# avt953.net
KiCad netlist of a schematic drawn in EAGLE
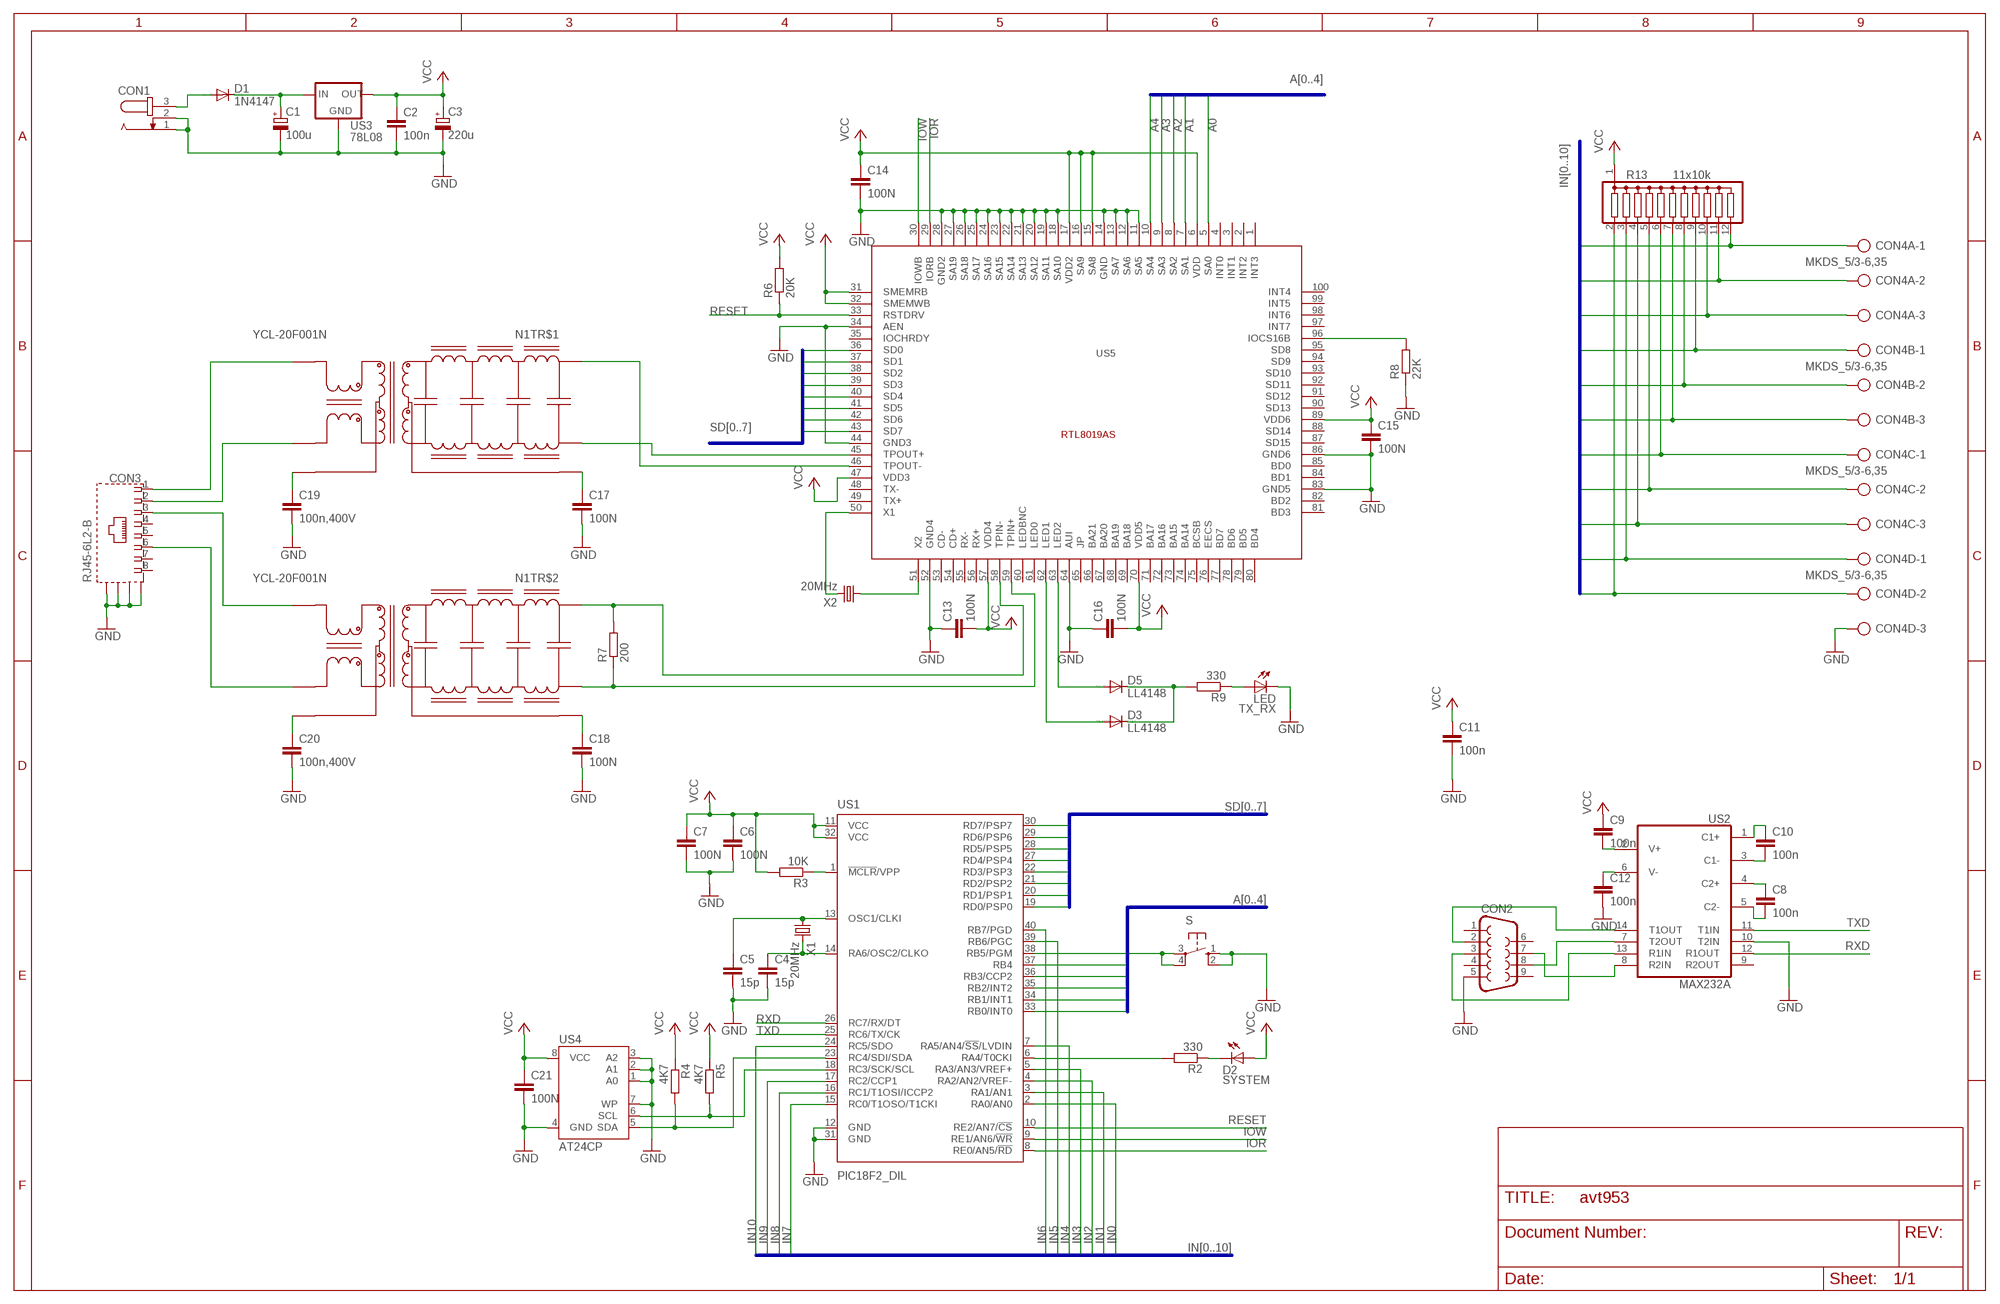
[diagram p0: schematic, sheet 1]

(export (version "E")
  (design (tool "Eeschema 10.0.6"))
  (components
    (comp (ref "C1")
      (value "100u")
      (footprint "eagle-import:TT2D5")
      (libsource (lib "eagle-import") (part "CPOL-EUTT2D5"))
    )
    (comp (ref "C2")
      (value "100n")
      (footprint "eagle-import:C1206K")
      (libsource (lib "eagle-import") (part "C-EUC1206K"))
    )
    (comp (ref "C3")
      (value "220u")
      (footprint "eagle-import:TT2D5")
      (libsource (lib "eagle-import") (part "CPOL-EUTT2D5"))
    )
    (comp (ref "C4")
      (value "15p")
      (footprint "eagle-import:C1206K")
      (libsource (lib "eagle-import") (part "C-EUC1206K"))
    )
    (comp (ref "C5")
      (value "15p")
      (footprint "eagle-import:C1206K")
      (libsource (lib "eagle-import") (part "C-EUC1206K"))
    )
    (comp (ref "C6")
      (value "100N")
      (footprint "eagle-import:C1206K")
      (libsource (lib "eagle-import") (part "C-EUC1206K"))
    )
    (comp (ref "C7")
      (value "100N")
      (footprint "eagle-import:C1206K")
      (libsource (lib "eagle-import") (part "C-EUC1206K"))
    )
    (comp (ref "C8")
      (value "100n")
      (footprint "eagle-import:C1206K")
      (libsource (lib "eagle-import") (part "C-EUC1206K"))
    )
    (comp (ref "C9")
      (value "100n")
      (footprint "eagle-import:C1206K")
      (libsource (lib "eagle-import") (part "C-EUC1206K"))
    )
    (comp (ref "C10")
      (value "100n")
      (footprint "eagle-import:C1206K")
      (libsource (lib "eagle-import") (part "C-EUC1206K"))
    )
    (comp (ref "C11")
      (value "100n")
      (footprint "eagle-import:C1206K")
      (libsource (lib "eagle-import") (part "C-EUC1206K"))
    )
    (comp (ref "C12")
      (value "100n")
      (footprint "eagle-import:C1206K")
      (libsource (lib "eagle-import") (part "C-EUC1206K"))
    )
    (comp (ref "C13")
      (value "100N")
      (footprint "eagle-import:C1206K")
      (libsource (lib "eagle-import") (part "C-EUC1206K"))
    )
    (comp (ref "C14")
      (value "100N")
      (footprint "eagle-import:C1206K")
      (libsource (lib "eagle-import") (part "C-EUC1206K"))
    )
    (comp (ref "C15")
      (value "100N")
      (footprint "eagle-import:C1206K")
      (libsource (lib "eagle-import") (part "C-EUC1206K"))
    )
    (comp (ref "C16")
      (value "100N")
      (footprint "eagle-import:C1206K")
      (libsource (lib "eagle-import") (part "C-EUC1206K"))
    )
    (comp (ref "C17")
      (value "100N")
      (footprint "eagle-import:C1206K")
      (libsource (lib "eagle-import") (part "C-EUC1206K"))
    )
    (comp (ref "C18")
      (value "100N")
      (footprint "eagle-import:C1206K")
      (libsource (lib "eagle-import") (part "C-EUC1206K"))
    )
    (comp (ref "C19")
      (value "100n,400V")
      (footprint "eagle-import:C075-032X103")
      (libsource (lib "eagle-import") (part "C-EU075-032X103"))
    )
    (comp (ref "C20")
      (value "100n,400V")
      (footprint "eagle-import:C075-032X103")
      (libsource (lib "eagle-import") (part "C-EU075-032X103"))
    )
    (comp (ref "C21")
      (value "100N")
      (footprint "eagle-import:C1206K")
      (libsource (lib "eagle-import") (part "C-EUC1206K"))
    )
    (comp (ref "CON1")
      (value "JACK-PLUG0")
      (footprint "eagle-import:SPC4077")
      (libsource (lib "eagle-import") (part "JACK-PLUG0"))
    )
    (comp (ref "CON2")
      (value "F09HP")
      (footprint "eagle-import:F09HP")
      (libsource (lib "eagle-import") (part "F09HP"))
    )
    (comp (ref "CON3")
      (value "RJ45-6L2-B")
      (footprint "eagle-import:RJ45-SHIELD2")
      (libsource (lib "eagle-import") (part "RJ452-B-6L"))
    )
    (comp (ref "CON4A")
      (value "MKDS_5/3-6,35")
      (footprint "eagle-import:MKDS_5_3-635")
      (fields (field (name "MF") "FARNELL") (field (name "MPN") "1714968"))
      (libsource (lib "eagle-import") (part "MKDS_5/3-6,35"))
    )
    (comp (ref "CON4B")
      (value "MKDS_5/3-6,35")
      (footprint "eagle-import:MKDS_5_3-635")
      (fields (field (name "MF") "FARNELL") (field (name "MPN") "1714968"))
      (libsource (lib "eagle-import") (part "MKDS_5/3-6,35"))
    )
    (comp (ref "CON4C")
      (value "MKDS_5/3-6,35")
      (footprint "eagle-import:MKDS_5_3-635")
      (fields (field (name "MF") "FARNELL") (field (name "MPN") "1714968"))
      (libsource (lib "eagle-import") (part "MKDS_5/3-6,35"))
    )
    (comp (ref "CON4D")
      (value "MKDS_5/3-6,35")
      (footprint "eagle-import:MKDS_5_3-635")
      (fields (field (name "MF") "FARNELL") (field (name "MPN") "1714968"))
      (libsource (lib "eagle-import") (part "MKDS_5/3-6,35"))
    )
    (comp (ref "D1")
      (value "1N4147")
      (footprint "eagle-import:DO35-10")
      (libsource (lib "eagle-import") (part "1N4148DO35-10"))
    )
    (comp (ref "D2")
      (value "SYSTEM")
      (footprint "eagle-import:LED5MM")
      (libsource (lib "eagle-import") (part "LED5MM"))
    )
    (comp (ref "D3")
      (value "LL4148")
      (footprint "eagle-import:SOD-123_MINI-SMA")
      (libsource (lib "eagle-import") (part "CGRM400-G1"))
    )
    (comp (ref "D5")
      (value "LL4148")
      (footprint "eagle-import:SOD-123_MINI-SMA")
      (libsource (lib "eagle-import") (part "CGRM400-G1"))
    )
    (comp (ref "LED")
      (value "TX_RX")
      (footprint "eagle-import:LED5MM")
      (libsource (lib "eagle-import") (part "LED5MM"))
    )
    (comp (ref "N1")
      (value "YCL-20F001N")
      (footprint "eagle-import:DIP")
      (libsource (lib "eagle-import") (part "YCL-20F001?N"))
    )
    (comp (ref "R2")
      (value "330")
      (footprint "eagle-import:M3216")
      (libsource (lib "eagle-import") (part "R-EU_M3216"))
    )
    (comp (ref "R3")
      (value "10K")
      (footprint "eagle-import:M3216")
      (libsource (lib "eagle-import") (part "R-EU_M3216"))
    )
    (comp (ref "R4")
      (value "4K7")
      (footprint "eagle-import:M3216")
      (libsource (lib "eagle-import") (part "R-EU_M3216"))
    )
    (comp (ref "R5")
      (value "4K7")
      (footprint "eagle-import:M3216")
      (libsource (lib "eagle-import") (part "R-EU_M3216"))
    )
    (comp (ref "R6")
      (value "20K")
      (footprint "eagle-import:M3216")
      (libsource (lib "eagle-import") (part "R-EU_M3216"))
    )
    (comp (ref "R7")
      (value "200")
      (footprint "eagle-import:M3216")
      (libsource (lib "eagle-import") (part "R-EU_M3216"))
    )
    (comp (ref "R8")
      (value "22K")
      (footprint "eagle-import:M3216")
      (libsource (lib "eagle-import") (part "R-EU_M3216"))
    )
    (comp (ref "R9")
      (value "330")
      (footprint "eagle-import:M3216")
      (libsource (lib "eagle-import") (part "R-EU_M3216"))
    )
    (comp (ref "R13")
      (value "11x10k")
      (footprint "eagle-import:SIL12")
      (libsource (lib "eagle-import") (part "G11R"))
    )
    (comp (ref "S")
      (value "10-XX")
      (footprint "eagle-import:B3F-10XX")
      (fields (field (name "MPN") "B3F-1000"))
      (libsource (lib "eagle-import") (part "10-XX"))
    )
    (comp (ref "US1")
      (value "PIC18F2_DIL")
      (footprint "eagle-import:DIL40")
      (libsource (lib "eagle-import") (part "PIC18F2_DIL"))
    )
    (comp (ref "US2")
      (value "MAX232A")
      (footprint "eagle-import:SO16L")
      (fields (field (name "MF") "MAXIM") (field (name "MPN") "MAX232ECWE+"))
      (libsource (lib "eagle-import") (part "MAX232ECWE"))
    )
    (comp (ref "US3")
      (value "78L08")
      (footprint "eagle-import:78XXL")
      (libsource (lib "eagle-import") (part "78XXL"))
    )
    (comp (ref "US4")
      (value "AT24CP")
      (footprint "eagle-import:DIL08")
      (fields (field (name "MPN") "AT24C1024BW-SH-B"))
      (libsource (lib "eagle-import") (part "AT24CP"))
    )
    (comp (ref "US5")
      (value "RTL8019AS")
      (footprint "eagle-import:RTL8019AS")
      (libsource (lib "eagle-import") (part "RTL8019AS"))
    )
    (comp (ref "X1")
      (value "20MHz")
      (footprint "eagle-import:HC49_S")
      (libsource (lib "eagle-import") (part "CRYSTALHC49S"))
    )
    (comp (ref "X2")
      (value "20MHz")
      (footprint "eagle-import:HC49_S")
      (libsource (lib "eagle-import") (part "CRYSTALHC49S"))
    )
  )
  (nets
    (net (code "1") (name "/A0") (class "Default")
      (node (ref "US1") (pin "33") (pinfunction "RB0/INT0_33") (pintype "bidirectional"))
      (node (ref "US5") (pin "5") (pinfunction "SA0_5") (pintype "bidirectional"))
    )
    (net (code "2") (name "/A1") (class "Default")
      (node (ref "US1") (pin "34") (pinfunction "RB1/INT1_34") (pintype "bidirectional"))
      (node (ref "US5") (pin "7") (pinfunction "SA1_7") (pintype "bidirectional"))
    )
    (net (code "3") (name "/A2") (class "Default")
      (node (ref "US1") (pin "35") (pinfunction "RB2/INT2_35") (pintype "bidirectional"))
      (node (ref "US5") (pin "8") (pinfunction "SA2_8") (pintype "bidirectional"))
    )
    (net (code "4") (name "/A3") (class "Default")
      (node (ref "US1") (pin "36") (pinfunction "RB3/CCP2_36") (pintype "bidirectional"))
      (node (ref "US5") (pin "9") (pinfunction "SA3_9") (pintype "bidirectional"))
    )
    (net (code "5") (name "/A4") (class "Default")
      (node (ref "US1") (pin "37") (pinfunction "RB4_37") (pintype "bidirectional"))
      (node (ref "US5") (pin "10") (pinfunction "SA4_10") (pintype "bidirectional"))
    )
    (net (code "7") (name "/IN0") (class "Default")
      (node (ref "CON4A") (pin "1") (pinfunction "KL_1") (pintype "passive"))
      (node (ref "R13") (pin "12") (pinfunction "12_12") (pintype "passive"))
      (node (ref "US1") (pin "2") (pinfunction "RA0/AN0_2") (pintype "bidirectional"))
    )
    (net (code "8") (name "/IN1") (class "Default")
      (node (ref "CON4A") (pin "2") (pinfunction "KL_2") (pintype "passive"))
      (node (ref "R13") (pin "11") (pinfunction "11_11") (pintype "passive"))
      (node (ref "US1") (pin "3") (pinfunction "RA1/AN1_3") (pintype "bidirectional"))
    )
    (net (code "9") (name "/IN2") (class "Default")
      (node (ref "CON4A") (pin "3") (pinfunction "KL_3") (pintype "passive"))
      (node (ref "R13") (pin "10") (pinfunction "10_10") (pintype "passive"))
      (node (ref "US1") (pin "4") (pinfunction "RA2/AN2/VREF-_4") (pintype "bidirectional"))
    )
    (net (code "10") (name "/IN3") (class "Default")
      (node (ref "CON4B") (pin "1") (pinfunction "KL_1") (pintype "passive"))
      (node (ref "R13") (pin "9") (pinfunction "9_9") (pintype "passive"))
      (node (ref "US1") (pin "5") (pinfunction "RA3/AN3/VREF+_5") (pintype "bidirectional"))
    )
    (net (code "11") (name "/IN4") (class "Default")
      (node (ref "CON4B") (pin "2") (pinfunction "KL_2") (pintype "passive"))
      (node (ref "R13") (pin "8") (pinfunction "8_8") (pintype "passive"))
      (node (ref "US1") (pin "7") (pinfunction "RA5/AN4/~{SS}/LVDIN_7") (pintype "bidirectional"))
    )
    (net (code "12") (name "/IN5") (class "Default")
      (node (ref "CON4B") (pin "3") (pinfunction "KL_3") (pintype "passive"))
      (node (ref "R13") (pin "7") (pinfunction "7_7") (pintype "passive"))
      (node (ref "US1") (pin "39") (pinfunction "RB6/PGC_39") (pintype "bidirectional"))
    )
    (net (code "13") (name "/IN6") (class "Default")
      (node (ref "CON4C") (pin "1") (pinfunction "KL_1") (pintype "passive"))
      (node (ref "R13") (pin "6") (pinfunction "6_6") (pintype "passive"))
      (node (ref "US1") (pin "40") (pinfunction "RB7/PGD_40") (pintype "bidirectional"))
    )
    (net (code "14") (name "/IN7") (class "Default")
      (node (ref "CON4C") (pin "2") (pinfunction "KL_2") (pintype "passive"))
      (node (ref "R13") (pin "5") (pinfunction "5_5") (pintype "passive"))
      (node (ref "US1") (pin "15") (pinfunction "RC0/T1OSO/T1CKI_15") (pintype "bidirectional"))
    )
    (net (code "15") (name "/IN8") (class "Default")
      (node (ref "CON4C") (pin "3") (pinfunction "KL_3") (pintype "passive"))
      (node (ref "R13") (pin "4") (pinfunction "4_4") (pintype "passive"))
      (node (ref "US1") (pin "16") (pinfunction "RC1/T1OSI/ICCP2_16") (pintype "bidirectional"))
    )
    (net (code "16") (name "/IN9") (class "Default")
      (node (ref "CON4D") (pin "1") (pinfunction "KL_1") (pintype "passive"))
      (node (ref "R13") (pin "3") (pinfunction "3_3") (pintype "passive"))
      (node (ref "US1") (pin "17") (pinfunction "RC2/CCP1_17") (pintype "bidirectional"))
    )
    (net (code "17") (name "/IN10") (class "Default")
      (node (ref "CON4D") (pin "2") (pinfunction "KL_2") (pintype "passive"))
      (node (ref "R13") (pin "2") (pinfunction "2_2") (pintype "passive"))
      (node (ref "US1") (pin "24") (pinfunction "RC5/SDO_24") (pintype "bidirectional"))
    )
    (net (code "19") (name "/IOR") (class "Default")
      (node (ref "US1") (pin "8") (pinfunction "RE0/AN5/~{RD}_8") (pintype "bidirectional"))
      (node (ref "US5") (pin "29") (pinfunction "IORB_29") (pintype "bidirectional"))
    )
    (net (code "20") (name "/IOW") (class "Default")
      (node (ref "US1") (pin "9") (pinfunction "RE1/AN6/~{WR}_9") (pintype "bidirectional"))
      (node (ref "US5") (pin "30") (pinfunction "IOWB_30") (pintype "bidirectional"))
    )
    (net (code "21") (name "/RESET") (class "Default")
      (node (ref "R6") (pin "1") (pinfunction "1_1") (pintype "passive"))
      (node (ref "US1") (pin "10") (pinfunction "RE2/AN7/~{CS}_10") (pintype "bidirectional"))
      (node (ref "US5") (pin "33") (pinfunction "RSTDRV_33") (pintype "bidirectional"))
    )
    (net (code "22") (name "/RXD") (class "Default")
      (node (ref "US1") (pin "26") (pinfunction "RC7/RX/DT_26") (pintype "bidirectional"))
      (node (ref "US2") (pin "12") (pinfunction "R1OUT_12") (pintype "output"))
    )
    (net (code "23") (name "/SD0") (class "Default")
      (node (ref "US1") (pin "19") (pinfunction "RD0/PSP0_19") (pintype "bidirectional"))
      (node (ref "US5") (pin "36") (pinfunction "SD0_36") (pintype "bidirectional"))
    )
    (net (code "24") (name "/SD1") (class "Default")
      (node (ref "US1") (pin "20") (pinfunction "RD1/PSP1_20") (pintype "bidirectional"))
      (node (ref "US5") (pin "37") (pinfunction "SD1_37") (pintype "bidirectional"))
    )
    (net (code "25") (name "/SD2") (class "Default")
      (node (ref "US1") (pin "21") (pinfunction "RD2/PSP2_21") (pintype "bidirectional"))
      (node (ref "US5") (pin "38") (pinfunction "SD2_38") (pintype "bidirectional"))
    )
    (net (code "26") (name "/SD3") (class "Default")
      (node (ref "US1") (pin "22") (pinfunction "RD3/PSP3_22") (pintype "bidirectional"))
      (node (ref "US5") (pin "39") (pinfunction "SD3_39") (pintype "bidirectional"))
    )
    (net (code "27") (name "/SD4") (class "Default")
      (node (ref "US1") (pin "27") (pinfunction "RD4/PSP4_27") (pintype "bidirectional"))
      (node (ref "US5") (pin "40") (pinfunction "SD4_40") (pintype "bidirectional"))
    )
    (net (code "28") (name "/SD5") (class "Default")
      (node (ref "US1") (pin "28") (pinfunction "RD5/PSP5_28") (pintype "bidirectional"))
      (node (ref "US5") (pin "41") (pinfunction "SD5_41") (pintype "bidirectional"))
    )
    (net (code "29") (name "/SD6") (class "Default")
      (node (ref "US1") (pin "29") (pinfunction "RD6/PSP6_29") (pintype "bidirectional"))
      (node (ref "US5") (pin "42") (pinfunction "SD6_42") (pintype "bidirectional"))
    )
    (net (code "30") (name "/SD7") (class "Default")
      (node (ref "US1") (pin "30") (pinfunction "RD7/PSP7_30") (pintype "bidirectional"))
      (node (ref "US5") (pin "43") (pinfunction "SD7_43") (pintype "bidirectional"))
    )
    (net (code "32") (name "/TXD") (class "Default")
      (node (ref "US1") (pin "25") (pinfunction "RC6/TX/CK_25") (pintype "bidirectional"))
      (node (ref "US2") (pin "11") (pinfunction "T1IN_11") (pintype "input"))
    )
    (net (code "33") (name "GND") (class "Default")
      (node (ref "C1") (pin "-") (pinfunction "-_-") (pintype "passive"))
      (node (ref "C11") (pin "2") (pinfunction "2_2") (pintype "passive"))
      (node (ref "C12") (pin "2") (pinfunction "2_2") (pintype "passive"))
      (node (ref "C13") (pin "1") (pinfunction "1_1") (pintype "passive"))
      (node (ref "C14") (pin "2") (pinfunction "2_2") (pintype "passive"))
      (node (ref "C15") (pin "2") (pinfunction "2_2") (pintype "passive"))
      (node (ref "C16") (pin "1") (pinfunction "1_1") (pintype "passive"))
      (node (ref "C17") (pin "2") (pinfunction "2_2") (pintype "passive"))
      (node (ref "C18") (pin "2") (pinfunction "2_2") (pintype "passive"))
      (node (ref "C19") (pin "2") (pinfunction "2_2") (pintype "passive"))
      (node (ref "C2") (pin "2") (pinfunction "2_2") (pintype "passive"))
      (node (ref "C20") (pin "2") (pinfunction "2_2") (pintype "passive"))
      (node (ref "C21") (pin "2") (pinfunction "2_2") (pintype "passive"))
      (node (ref "C3") (pin "-") (pinfunction "-_-") (pintype "passive"))
      (node (ref "C4") (pin "2") (pinfunction "2_2") (pintype "passive"))
      (node (ref "C5") (pin "2") (pinfunction "2_2") (pintype "passive"))
      (node (ref "C6") (pin "2") (pinfunction "2_2") (pintype "passive"))
      (node (ref "C7") (pin "2") (pinfunction "2_2") (pintype "passive"))
      (node (ref "CON1") (pin "1") (pinfunction "1_1") (pintype "passive"))
      (node (ref "CON1") (pin "2") (pinfunction "2_2") (pintype "passive"))
      (node (ref "CON2") (pin "5") (pinfunction "5_5") (pintype "passive"))
      (node (ref "CON3") (pin "S1") (pinfunction "S_S1") (pintype "passive"))
      (node (ref "CON3") (pin "S2") (pinfunction "S_S2") (pintype "passive"))
      (node (ref "CON3") (pin "S3") (pinfunction "S_S3") (pintype "passive"))
      (node (ref "CON3") (pin "S4") (pinfunction "S_S4") (pintype "passive"))
      (node (ref "CON4D") (pin "3") (pinfunction "KL_3") (pintype "passive"))
      (node (ref "LED") (pin "K") (pinfunction "C_K") (pintype "passive"))
      (node (ref "R8") (pin "1") (pinfunction "1_1") (pintype "passive"))
      (node (ref "S") (pin "1") (pinfunction "S_1") (pintype "passive"))
      (node (ref "S") (pin "2") (pinfunction "S1_2") (pintype "passive"))
      (node (ref "US1") (pin "12") (pinfunction "GND_12") (pintype "power_in"))
      (node (ref "US1") (pin "31") (pinfunction "GND_31") (pintype "power_in"))
      (node (ref "US2") (pin "10") (pinfunction "T2IN_10") (pintype "input"))
      (node (ref "US3") (pin "GND") (pinfunction "GND_GND") (pintype "input"))
      (node (ref "US4") (pin "1") (pinfunction "A0_1") (pintype "input"))
      (node (ref "US4") (pin "2") (pinfunction "A1_2") (pintype "input"))
      (node (ref "US4") (pin "3") (pinfunction "A2_3") (pintype "input"))
      (node (ref "US4") (pin "4") (pinfunction "GND_4") (pintype "power_in"))
      (node (ref "US4") (pin "7") (pinfunction "WP_7") (pintype "input"))
      (node (ref "US5") (pin "11") (pinfunction "SA5_11") (pintype "bidirectional"))
      (node (ref "US5") (pin "12") (pinfunction "SA6_12") (pintype "bidirectional"))
      (node (ref "US5") (pin "13") (pinfunction "SA7_13") (pintype "bidirectional"))
      (node (ref "US5") (pin "14") (pinfunction "GND_14") (pintype "power_in"))
      (node (ref "US5") (pin "18") (pinfunction "SA10_18") (pintype "bidirectional"))
      (node (ref "US5") (pin "19") (pinfunction "SA11_19") (pintype "bidirectional"))
      (node (ref "US5") (pin "20") (pinfunction "SA12_20") (pintype "bidirectional"))
      (node (ref "US5") (pin "21") (pinfunction "SA13_21") (pintype "bidirectional"))
      (node (ref "US5") (pin "22") (pinfunction "SA14_22") (pintype "bidirectional"))
      (node (ref "US5") (pin "23") (pinfunction "SA15_23") (pintype "bidirectional"))
      (node (ref "US5") (pin "24") (pinfunction "SA16_24") (pintype "bidirectional"))
      (node (ref "US5") (pin "25") (pinfunction "SA17_25") (pintype "bidirectional"))
      (node (ref "US5") (pin "26") (pinfunction "SA18_26") (pintype "bidirectional"))
      (node (ref "US5") (pin "27") (pinfunction "SA19_27") (pintype "bidirectional"))
      (node (ref "US5") (pin "28") (pinfunction "GND2_28") (pintype "power_in"))
      (node (ref "US5") (pin "34") (pinfunction "AEN_34") (pintype "bidirectional"))
      (node (ref "US5") (pin "44") (pinfunction "GND3_44") (pintype "power_in"))
      (node (ref "US5") (pin "52") (pinfunction "GND4_52") (pintype "power_in"))
      (node (ref "US5") (pin "64") (pinfunction "AUI_64") (pintype "bidirectional"))
      (node (ref "US5") (pin "83") (pinfunction "GND5_83") (pintype "power_in"))
      (node (ref "US5") (pin "86") (pinfunction "GND6_86") (pintype "power_in"))
    )
    (net (code "34") (name "Net-(C1-Pad+)") (class "Default")
      (node (ref "C1") (pin "+") (pinfunction "+_+") (pintype "passive"))
      (node (ref "D1") (pin "C") (pinfunction "C_C") (pintype "passive"))
      (node (ref "US3") (pin "IN") (pinfunction "IN_IN") (pintype "input"))
    )
    (net (code "35") (name "Net-(C17-Pad1)") (class "Default")
      (node (ref "C17") (pin "1") (pinfunction "1_1") (pintype "passive"))
      (node (ref "N1") (pin "P$2") (pinfunction "P$2_P$2") (pintype "passive"))
    )
    (net (code "36") (name "Net-(CON1-Pad3)") (class "Default")
      (node (ref "CON1") (pin "3") (pinfunction "3_3") (pintype "passive"))
      (node (ref "D1") (pin "A") (pinfunction "A_A") (pintype "passive"))
    )
    (net (code "37") (name "Net-(D2-C)") (class "Default")
      (node (ref "D2") (pin "K") (pinfunction "C_K") (pintype "passive"))
      (node (ref "R2") (pin "1") (pinfunction "1_1") (pintype "passive"))
    )
    (net (code "38") (name "Net-(D3-PadC)") (class "Default")
      (node (ref "D3") (pin "C") (pinfunction "C_C") (pintype "passive"))
      (node (ref "D5") (pin "C") (pinfunction "C_C") (pintype "passive"))
      (node (ref "R9") (pin "2") (pinfunction "2_2") (pintype "passive"))
    )
    (net (code "39") (name "Net-(LED-PadA)") (class "Default")
      (node (ref "LED") (pin "A") (pinfunction "A_A") (pintype "passive"))
      (node (ref "R9") (pin "1") (pinfunction "1_1") (pintype "passive"))
    )
    (net (code "40") (name "Net-(N1A-P$4)") (class "Default")
      (node (ref "CON3") (pin "1") (pinfunction "1_1") (pintype "passive"))
      (node (ref "N1") (pin "P$16") (pinfunction "P$4_P$16") (pintype "passive"))
    )
    (net (code "41") (name "Net-(N1A-P$5)") (class "Default")
      (node (ref "C19") (pin "1") (pinfunction "1_1") (pintype "passive"))
      (node (ref "N1") (pin "P$15") (pinfunction "P$5_P$15") (pintype "passive"))
    )
    (net (code "42") (name "Net-(N1A-P$6)") (class "Default")
      (node (ref "CON3") (pin "2") (pinfunction "2_2") (pintype "passive"))
      (node (ref "N1") (pin "P$14") (pinfunction "P$6_P$14") (pintype "passive"))
    )
    (net (code "43") (name "Net-(N1B-P$1)") (class "Default")
      (node (ref "N1") (pin "P$6") (pinfunction "P$1_P$6") (pintype "passive"))
      (node (ref "R7") (pin "2") (pinfunction "2_2") (pintype "passive"))
      (node (ref "US5") (pin "58") (pinfunction "TPIN-_58") (pintype "bidirectional"))
    )
    (net (code "44") (name "Net-(N1B-P$2)") (class "Default")
      (node (ref "C18") (pin "1") (pinfunction "1_1") (pintype "passive"))
      (node (ref "N1") (pin "P$7") (pinfunction "P$2_P$7") (pintype "passive"))
    )
    (net (code "45") (name "Net-(N1B-P$3)") (class "Default")
      (node (ref "N1") (pin "P$8") (pinfunction "P$3_P$8") (pintype "passive"))
      (node (ref "R7") (pin "1") (pinfunction "1_1") (pintype "passive"))
      (node (ref "US5") (pin "59") (pinfunction "TPIN+_59") (pintype "bidirectional"))
    )
    (net (code "46") (name "Net-(N1B-P$4)") (class "Default")
      (node (ref "CON3") (pin "3") (pinfunction "3_3") (pintype "passive"))
      (node (ref "N1") (pin "P$11") (pinfunction "P$4_P$11") (pintype "passive"))
    )
    (net (code "47") (name "Net-(N1B-P$5)") (class "Default")
      (node (ref "C20") (pin "1") (pinfunction "1_1") (pintype "passive"))
      (node (ref "N1") (pin "P$10") (pinfunction "P$5_P$10") (pintype "passive"))
    )
    (net (code "48") (name "Net-(N1B-P$6)") (class "Default")
      (node (ref "CON3") (pin "6") (pinfunction "6_6") (pintype "passive"))
      (node (ref "N1") (pin "P$9") (pinfunction "P$6_P$9") (pintype "passive"))
    )
    (net (code "49") (name "Net-(S-P)") (class "Default")
      (node (ref "S") (pin "3") (pinfunction "P_3") (pintype "passive"))
      (node (ref "S") (pin "4") (pinfunction "P1_4") (pintype "passive"))
      (node (ref "US1") (pin "38") (pinfunction "RB5/PGM_38") (pintype "bidirectional"))
    )
    (net (code "50") (name "Net-(US1-OSC1{slash}CLKI)") (class "Default")
      (node (ref "C5") (pin "1") (pinfunction "1_1") (pintype "passive"))
      (node (ref "US1") (pin "13") (pinfunction "OSC1/CLKI_13") (pintype "input"))
      (node (ref "X1") (pin "1") (pinfunction "1_1") (pintype "passive"))
    )
    (net (code "51") (name "Net-(US1-RA4{slash}T0CKI)") (class "Default")
      (node (ref "R2") (pin "2") (pinfunction "2_2") (pintype "passive"))
      (node (ref "US1") (pin "6") (pinfunction "RA4/T0CKI_6") (pintype "bidirectional"))
    )
    (net (code "52") (name "Net-(US1-RA6{slash}OSC2{slash}CLKO)") (class "Default")
      (node (ref "C4") (pin "1") (pinfunction "1_1") (pintype "passive"))
      (node (ref "US1") (pin "14") (pinfunction "RA6/OSC2/CLKO_14") (pintype "output"))
      (node (ref "X1") (pin "2") (pinfunction "2_2") (pintype "passive"))
    )
    (net (code "53") (name "Net-(US1-RC3{slash}SCK{slash}SCL)") (class "Default")
      (node (ref "R5") (pin "2") (pinfunction "2_2") (pintype "passive"))
      (node (ref "US1") (pin "18") (pinfunction "RC3/SCK/SCL_18") (pintype "bidirectional"))
      (node (ref "US4") (pin "6") (pinfunction "SCL_6") (pintype "bidirectional"))
    )
    (net (code "54") (name "Net-(US1-RC4{slash}SDI{slash}SDA)") (class "Default")
      (node (ref "R4") (pin "2") (pinfunction "2_2") (pintype "passive"))
      (node (ref "US1") (pin "23") (pinfunction "RC4/SDI/SDA_23") (pintype "bidirectional"))
      (node (ref "US4") (pin "5") (pinfunction "SDA_5") (pintype "bidirectional"))
    )
    (net (code "55") (name "Net-(US1-~{MCLR}{slash}VPP)") (class "Default")
      (node (ref "R3") (pin "1") (pinfunction "1_1") (pintype "passive"))
      (node (ref "US1") (pin "1") (pinfunction "~{MCLR}/VPP_1") (pintype "input"))
    )
    (net (code "56") (name "Net-(US2A-C1+)") (class "Default")
      (node (ref "C10") (pin "1") (pinfunction "1_1") (pintype "passive"))
      (node (ref "US2") (pin "1") (pinfunction "C1+_1") (pintype "bidirectional"))
    )
    (net (code "57") (name "Net-(US2A-C1-)") (class "Default")
      (node (ref "C10") (pin "2") (pinfunction "2_2") (pintype "passive"))
      (node (ref "US2") (pin "3") (pinfunction "C1-_3") (pintype "bidirectional"))
    )
    (net (code "58") (name "Net-(US2A-C2+)") (class "Default")
      (node (ref "C8") (pin "1") (pinfunction "1_1") (pintype "passive"))
      (node (ref "US2") (pin "4") (pinfunction "C2+_4") (pintype "bidirectional"))
    )
    (net (code "59") (name "Net-(US2A-C2-)") (class "Default")
      (node (ref "C8") (pin "2") (pinfunction "2_2") (pintype "passive"))
      (node (ref "US2") (pin "5") (pinfunction "C2-_5") (pintype "bidirectional"))
    )
    (net (code "60") (name "Net-(US2A-R1IN)") (class "Default")
      (node (ref "CON2") (pin "3") (pinfunction "3_3") (pintype "passive"))
      (node (ref "US2") (pin "13") (pinfunction "R1IN_13") (pintype "input"))
    )
    (net (code "61") (name "Net-(US2A-R2IN)") (class "Default")
      (node (ref "CON2") (pin "7") (pinfunction "7_7") (pintype "passive"))
      (node (ref "US2") (pin "8") (pinfunction "R2IN_8") (pintype "input"))
    )
    (net (code "62") (name "Net-(US2A-T1OUT)") (class "Default")
      (node (ref "CON2") (pin "2") (pinfunction "2_2") (pintype "passive"))
      (node (ref "US2") (pin "14") (pinfunction "T1OUT_14") (pintype "output"))
    )
    (net (code "63") (name "Net-(US2A-T2OUT)") (class "Default")
      (node (ref "CON2") (pin "8") (pinfunction "8_8") (pintype "passive"))
      (node (ref "US2") (pin "7") (pinfunction "T2OUT_7") (pintype "output"))
    )
    (net (code "64") (name "Net-(US2A-V+)") (class "Default")
      (node (ref "C9") (pin "2") (pinfunction "2_2") (pintype "passive"))
      (node (ref "US2") (pin "2") (pinfunction "V+_2") (pintype "bidirectional"))
    )
    (net (code "65") (name "Net-(US2A-V-)") (class "Default")
      (node (ref "C12") (pin "1") (pinfunction "1_1") (pintype "passive"))
      (node (ref "US2") (pin "6") (pinfunction "V-_6") (pintype "bidirectional"))
    )
    (net (code "66") (name "Net-(US5-IOCS16B)") (class "Default")
      (node (ref "R8") (pin "2") (pinfunction "2_2") (pintype "passive"))
      (node (ref "US5") (pin "96") (pinfunction "IOCS16B_96") (pintype "bidirectional"))
    )
    (net (code "67") (name "Net-(US5-LED1)") (class "Default")
      (node (ref "D3") (pin "A") (pinfunction "A_A") (pintype "passive"))
      (node (ref "US5") (pin "62") (pinfunction "LED1_62") (pintype "bidirectional"))
    )
    (net (code "68") (name "Net-(US5-LED2)") (class "Default")
      (node (ref "D5") (pin "A") (pinfunction "A_A") (pintype "passive"))
      (node (ref "US5") (pin "63") (pinfunction "LED2_63") (pintype "bidirectional"))
    )
    (net (code "69") (name "Net-(US5-TPOUT+)") (class "Default")
      (node (ref "N1") (pin "P$3") (pinfunction "P$3_P$3") (pintype "passive"))
      (node (ref "US5") (pin "45") (pinfunction "TPOUT+_45") (pintype "bidirectional"))
    )
    (net (code "70") (name "Net-(US5-TPOUT-)") (class "Default")
      (node (ref "N1") (pin "P$1") (pinfunction "P$1_P$1") (pintype "passive"))
      (node (ref "US5") (pin "46") (pinfunction "TPOUT-_46") (pintype "bidirectional"))
    )
    (net (code "71") (name "Net-(US5-X1)") (class "Default")
      (node (ref "US5") (pin "50") (pinfunction "X1_50") (pintype "bidirectional"))
      (node (ref "X2") (pin "2") (pinfunction "2_2") (pintype "passive"))
    )
    (net (code "72") (name "Net-(US5-X2)") (class "Default")
      (node (ref "US5") (pin "51") (pinfunction "X2_51") (pintype "bidirectional"))
      (node (ref "X2") (pin "1") (pinfunction "1_1") (pintype "passive"))
    )
    (net (code "73") (name "VCC") (class "Default")
      (node (ref "C11") (pin "1") (pinfunction "1_1") (pintype "passive"))
      (node (ref "C13") (pin "2") (pinfunction "2_2") (pintype "passive"))
      (node (ref "C14") (pin "1") (pinfunction "1_1") (pintype "passive"))
      (node (ref "C15") (pin "1") (pinfunction "1_1") (pintype "passive"))
      (node (ref "C16") (pin "2") (pinfunction "2_2") (pintype "passive"))
      (node (ref "C2") (pin "1") (pinfunction "1_1") (pintype "passive"))
      (node (ref "C21") (pin "1") (pinfunction "1_1") (pintype "passive"))
      (node (ref "C3") (pin "+") (pinfunction "+_+") (pintype "passive"))
      (node (ref "C6") (pin "1") (pinfunction "1_1") (pintype "passive"))
      (node (ref "C7") (pin "1") (pinfunction "1_1") (pintype "passive"))
      (node (ref "C9") (pin "1") (pinfunction "1_1") (pintype "passive"))
      (node (ref "D2") (pin "A") (pinfunction "A_A") (pintype "passive"))
      (node (ref "R13") (pin "1") (pinfunction "1_1") (pintype "passive"))
      (node (ref "R3") (pin "2") (pinfunction "2_2") (pintype "passive"))
      (node (ref "R4") (pin "1") (pinfunction "1_1") (pintype "passive"))
      (node (ref "R5") (pin "1") (pinfunction "1_1") (pintype "passive"))
      (node (ref "R6") (pin "2") (pinfunction "2_2") (pintype "passive"))
      (node (ref "US1") (pin "11") (pinfunction "VCC_11") (pintype "power_in"))
      (node (ref "US1") (pin "32") (pinfunction "VCC_32") (pintype "power_in"))
      (node (ref "US3") (pin "OUT") (pinfunction "OUT_OUT") (pintype "passive"))
      (node (ref "US4") (pin "8") (pinfunction "VCC_8") (pintype "power_in"))
      (node (ref "US5") (pin "15") (pinfunction "SA8_15") (pintype "bidirectional"))
      (node (ref "US5") (pin "16") (pinfunction "SA9_16") (pintype "bidirectional"))
      (node (ref "US5") (pin "17") (pinfunction "VDD2_17") (pintype "power_in"))
      (node (ref "US5") (pin "31") (pinfunction "SMEMRB_31") (pintype "bidirectional"))
      (node (ref "US5") (pin "32") (pinfunction "SMEMWB_32") (pintype "bidirectional"))
      (node (ref "US5") (pin "47") (pinfunction "VDD3_47") (pintype "power_in"))
      (node (ref "US5") (pin "57") (pinfunction "VDD4_57") (pintype "power_in"))
      (node (ref "US5") (pin "6") (pinfunction "VDD_6") (pintype "power_in"))
      (node (ref "US5") (pin "70") (pinfunction "VDD5_70") (pintype "power_in"))
      (node (ref "US5") (pin "89") (pinfunction "VDD6_89") (pintype "power_in"))
    )
    (net (code "74") (name "unconnected-(CON2-Pad1)") (class "Default")
      (node (ref "CON2") (pin "1") (pinfunction "1_1") (pintype "passive"))
    )
    (net (code "75") (name "unconnected-(CON2-Pad4)") (class "Default")
      (node (ref "CON2") (pin "4") (pinfunction "4_4") (pintype "passive"))
    )
    (net (code "76") (name "unconnected-(CON2-Pad6)") (class "Default")
      (node (ref "CON2") (pin "6") (pinfunction "6_6") (pintype "passive"))
    )
    (net (code "77") (name "unconnected-(CON2-Pad9)") (class "Default")
      (node (ref "CON2") (pin "9") (pinfunction "9_9") (pintype "passive"))
    )
    (net (code "78") (name "unconnected-(CON3-Pad4)") (class "Default")
      (node (ref "CON3") (pin "4") (pinfunction "4_4") (pintype "passive"))
    )
    (net (code "79") (name "unconnected-(CON3-Pad5)") (class "Default")
      (node (ref "CON3") (pin "5") (pinfunction "5_5") (pintype "passive"))
    )
    (net (code "80") (name "unconnected-(CON3-Pad7)") (class "Default")
      (node (ref "CON3") (pin "7") (pinfunction "7_7") (pintype "passive"))
    )
    (net (code "81") (name "unconnected-(CON3-Pad8)") (class "Default")
      (node (ref "CON3") (pin "8") (pinfunction "8_8") (pintype "passive"))
    )
    (net (code "82") (name "unconnected-(US2A-R2OUT-Pad9)") (class "Default")
      (node (ref "US2") (pin "9") (pinfunction "R2OUT_9") (pintype "output"))
    )
    (net (code "83") (name "unconnected-(US5-BA14-Pad74)") (class "Default")
      (node (ref "US5") (pin "74") (pinfunction "BA14_74") (pintype "bidirectional"))
    )
    (net (code "84") (name "unconnected-(US5-BA15-Pad73)") (class "Default")
      (node (ref "US5") (pin "73") (pinfunction "BA15_73") (pintype "bidirectional"))
    )
    (net (code "85") (name "unconnected-(US5-BA16-Pad72)") (class "Default")
      (node (ref "US5") (pin "72") (pinfunction "BA16_72") (pintype "bidirectional"))
    )
    (net (code "86") (name "unconnected-(US5-BA17-Pad71)") (class "Default")
      (node (ref "US5") (pin "71") (pinfunction "BA17_71") (pintype "bidirectional"))
    )
    (net (code "87") (name "unconnected-(US5-BA18-Pad69)") (class "Default")
      (node (ref "US5") (pin "69") (pinfunction "BA18_69") (pintype "bidirectional"))
    )
    (net (code "88") (name "unconnected-(US5-BA19-Pad68)") (class "Default")
      (node (ref "US5") (pin "68") (pinfunction "BA19_68") (pintype "bidirectional"))
    )
    (net (code "89") (name "unconnected-(US5-BA20-Pad67)") (class "Default")
      (node (ref "US5") (pin "67") (pinfunction "BA20_67") (pintype "bidirectional"))
    )
    (net (code "90") (name "unconnected-(US5-BA21-Pad66)") (class "Default")
      (node (ref "US5") (pin "66") (pinfunction "BA21_66") (pintype "bidirectional"))
    )
    (net (code "91") (name "unconnected-(US5-BCSB-Pad75)") (class "Default")
      (node (ref "US5") (pin "75") (pinfunction "BCSB_75") (pintype "bidirectional"))
    )
    (net (code "92") (name "unconnected-(US5-BD0-Pad85)") (class "Default")
      (node (ref "US5") (pin "85") (pinfunction "BD0_85") (pintype "bidirectional"))
    )
    (net (code "93") (name "unconnected-(US5-BD1-Pad84)") (class "Default")
      (node (ref "US5") (pin "84") (pinfunction "BD1_84") (pintype "bidirectional"))
    )
    (net (code "94") (name "unconnected-(US5-BD2-Pad82)") (class "Default")
      (node (ref "US5") (pin "82") (pinfunction "BD2_82") (pintype "bidirectional"))
    )
    (net (code "95") (name "unconnected-(US5-BD3-Pad81)") (class "Default")
      (node (ref "US5") (pin "81") (pinfunction "BD3_81") (pintype "bidirectional"))
    )
    (net (code "96") (name "unconnected-(US5-BD4-Pad80)") (class "Default")
      (node (ref "US5") (pin "80") (pinfunction "BD4_80") (pintype "bidirectional"))
    )
    (net (code "97") (name "unconnected-(US5-BD5-Pad79)") (class "Default")
      (node (ref "US5") (pin "79") (pinfunction "BD5_79") (pintype "bidirectional"))
    )
    (net (code "98") (name "unconnected-(US5-BD6-Pad78)") (class "Default")
      (node (ref "US5") (pin "78") (pinfunction "BD6_78") (pintype "bidirectional"))
    )
    (net (code "99") (name "unconnected-(US5-BD7-Pad77)") (class "Default")
      (node (ref "US5") (pin "77") (pinfunction "BD7_77") (pintype "bidirectional"))
    )
    (net (code "100") (name "unconnected-(US5-CD+-Pad54)") (class "Default")
      (node (ref "US5") (pin "54") (pinfunction "CD+_54") (pintype "bidirectional"))
    )
    (net (code "101") (name "unconnected-(US5-CD--Pad53)") (class "Default")
      (node (ref "US5") (pin "53") (pinfunction "CD-_53") (pintype "bidirectional"))
    )
    (net (code "102") (name "unconnected-(US5-EECS-Pad76)") (class "Default")
      (node (ref "US5") (pin "76") (pinfunction "EECS_76") (pintype "bidirectional"))
    )
    (net (code "103") (name "unconnected-(US5-INT0-Pad4)") (class "Default")
      (node (ref "US5") (pin "4") (pinfunction "INT0_4") (pintype "bidirectional"))
    )
    (net (code "104") (name "unconnected-(US5-INT1-Pad3)") (class "Default")
      (node (ref "US5") (pin "3") (pinfunction "INT1_3") (pintype "bidirectional"))
    )
    (net (code "105") (name "unconnected-(US5-INT2-Pad2)") (class "Default")
      (node (ref "US5") (pin "2") (pinfunction "INT2_2") (pintype "bidirectional"))
    )
    (net (code "106") (name "unconnected-(US5-INT3-Pad1)") (class "Default")
      (node (ref "US5") (pin "1") (pinfunction "INT3_1") (pintype "bidirectional"))
    )
    (net (code "107") (name "unconnected-(US5-INT4-Pad100)") (class "Default")
      (node (ref "US5") (pin "100") (pinfunction "INT4_100") (pintype "bidirectional"))
    )
    (net (code "108") (name "unconnected-(US5-INT5-Pad99)") (class "Default")
      (node (ref "US5") (pin "99") (pinfunction "INT5_99") (pintype "bidirectional"))
    )
    (net (code "109") (name "unconnected-(US5-INT6-Pad98)") (class "Default")
      (node (ref "US5") (pin "98") (pinfunction "INT6_98") (pintype "bidirectional"))
    )
    (net (code "110") (name "unconnected-(US5-INT7-Pad97)") (class "Default")
      (node (ref "US5") (pin "97") (pinfunction "INT7_97") (pintype "bidirectional"))
    )
    (net (code "111") (name "unconnected-(US5-IOCHRDY-Pad35)") (class "Default")
      (node (ref "US5") (pin "35") (pinfunction "IOCHRDY_35") (pintype "bidirectional"))
    )
    (net (code "112") (name "unconnected-(US5-JP-Pad65)") (class "Default")
      (node (ref "US5") (pin "65") (pinfunction "JP_65") (pintype "bidirectional"))
    )
    (net (code "113") (name "unconnected-(US5-LED0-Pad61)") (class "Default")
      (node (ref "US5") (pin "61") (pinfunction "LED0_61") (pintype "bidirectional"))
    )
    (net (code "114") (name "unconnected-(US5-LEDBNC-Pad60)") (class "Default")
      (node (ref "US5") (pin "60") (pinfunction "LEDBNC_60") (pintype "bidirectional"))
    )
    (net (code "115") (name "unconnected-(US5-RX+-Pad56)") (class "Default")
      (node (ref "US5") (pin "56") (pinfunction "RX+_56") (pintype "bidirectional"))
    )
    (net (code "116") (name "unconnected-(US5-RX--Pad55)") (class "Default")
      (node (ref "US5") (pin "55") (pinfunction "RX-_55") (pintype "bidirectional"))
    )
    (net (code "117") (name "unconnected-(US5-SD8-Pad95)") (class "Default")
      (node (ref "US5") (pin "95") (pinfunction "SD8_95") (pintype "bidirectional"))
    )
    (net (code "118") (name "unconnected-(US5-SD9-Pad94)") (class "Default")
      (node (ref "US5") (pin "94") (pinfunction "SD9_94") (pintype "bidirectional"))
    )
    (net (code "119") (name "unconnected-(US5-SD10-Pad93)") (class "Default")
      (node (ref "US5") (pin "93") (pinfunction "SD10_93") (pintype "bidirectional"))
    )
    (net (code "120") (name "unconnected-(US5-SD11-Pad92)") (class "Default")
      (node (ref "US5") (pin "92") (pinfunction "SD11_92") (pintype "bidirectional"))
    )
    (net (code "121") (name "unconnected-(US5-SD12-Pad91)") (class "Default")
      (node (ref "US5") (pin "91") (pinfunction "SD12_91") (pintype "bidirectional"))
    )
    (net (code "122") (name "unconnected-(US5-SD13-Pad90)") (class "Default")
      (node (ref "US5") (pin "90") (pinfunction "SD13_90") (pintype "bidirectional"))
    )
    (net (code "123") (name "unconnected-(US5-SD14-Pad88)") (class "Default")
      (node (ref "US5") (pin "88") (pinfunction "SD14_88") (pintype "bidirectional"))
    )
    (net (code "124") (name "unconnected-(US5-SD15-Pad87)") (class "Default")
      (node (ref "US5") (pin "87") (pinfunction "SD15_87") (pintype "bidirectional"))
    )
    (net (code "125") (name "unconnected-(US5-TX+-Pad49)") (class "Default")
      (node (ref "US5") (pin "49") (pinfunction "TX+_49") (pintype "bidirectional"))
    )
    (net (code "126") (name "unconnected-(US5-TX--Pad48)") (class "Default")
      (node (ref "US5") (pin "48") (pinfunction "TX-_48") (pintype "bidirectional"))
    )
  )
)
